# Battery_protector.net
KiCad netlist of a schematic drawn in Altium Designer
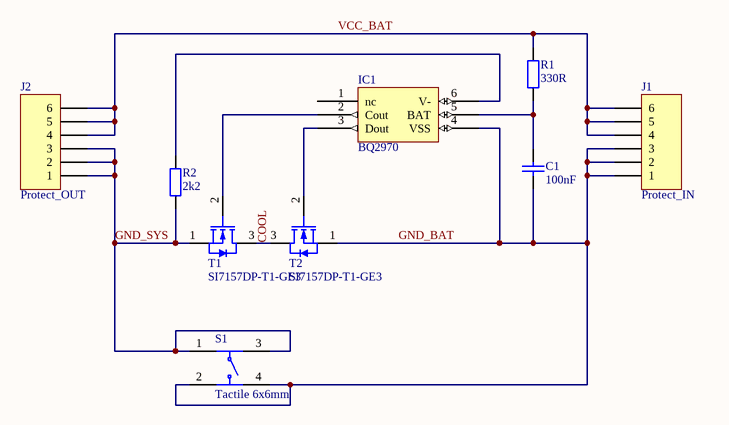
[diagram p0: Battery protector.SchDoc]

(export (version "E")
  (design (tool "Eeschema 10.0.6"))
  (components
    (comp (ref "C1")
      (value "100nF")
      (footprint "0603 cap")
      (description "Capacitor")
      (fields (field (name "VOLTAGE") ">5V"))
      (libsource (lib "IKSOR_LIB_main") (part "Capacitor NP"))
    )
    (comp (ref "IC1")
      (value "BQ2970")
      (footprint "PWSON-6")
      (description "Battery protection IC")
      (libsource (lib "IKSOR_LIB_main") (part "BQ2970"))
    )
    (comp (ref "J1")
      (value "Protect_IN")
      (footprint "HDR1X6")
      (description "Header, 6-Pin")
      (fields (field (name "PUBLISHER") "Altium Limited"))
      (libsource (lib "Miscellaneous Connectors") (part "Header 6"))
    )
    (comp (ref "J2")
      (value "Protect_OUT")
      (footprint "HDR1X6")
      (description "Header, 6-Pin")
      (fields (field (name "PUBLISHER") "Altium Limited"))
      (libsource (lib "") (part "Header 6_1"))
    )
    (comp (ref "R1")
      (value "330R")
      (footprint "0603 RES")
      (description "Resistor SMD")
      (fields (field (name "Comment") "Resistor generic"))
      (libsource (lib "IKSOR_LIB_main") (part "Resistor"))
    )
    (comp (ref "R2")
      (value "2k2")
      (footprint "0603 RES")
      (description "Resistor SMD")
      (fields (field (name "Comment") "Resistor generic"))
      (libsource (lib "IKSOR_LIB_main") (part "Resistor"))
    )
    (comp (ref "S1")
      (value "Tactile 6x6mm")
      (footprint "4301x20438x6")
      (description "WS-TASV 6x6 mm SMD")
      (fields
        (field (name "PARTNO") "430152043826")
        (field (name "MANUFACTURER") "Wurth Elektronik")
        (field (name "CREATED BY") "Baojun Chen")
      )
      (libsource (lib "ALTIUM-WS-TASV-rev16a") (part "WS-TASV, 430152043826"))
    )
    (comp (ref "T1")
      (value "SI7157DP-T1-GE3")
      (footprint "TDSON-8")
      (description "MOSFET N")
      (fields (field (name "Comment") "MOSFET-N"))
      (libsource (lib "IKSOR_LIB_main") (part "MOSFET-N"))
    )
    (comp (ref "T2")
      (value "SI7157DP-T1-GE3")
      (footprint "TDSON-8")
      (description "MOSFET N")
      (fields (field (name "Comment") "MOSFET-N"))
      (libsource (lib "IKSOR_LIB_main") (part "MOSFET-N"))
    )
  )
  (nets
    (net (code "1") (name "/COOL") (class "Default")
      (node (ref "T1") (pin "3") (pinfunction "D_3") (pintype "passive"))
      (node (ref "T2") (pin "3") (pinfunction "D_3") (pintype "passive"))
    )
    (net (code "2") (name "/GND_BAT") (class "Default")
      (node (ref "C1") (pin "1") (pinfunction "1_1") (pintype "passive"))
      (node (ref "IC1") (pin "4") (pinfunction "VSS_4") (pintype "bidirectional"))
      (node (ref "J1") (pin "1") (pinfunction "1_1") (pintype "passive"))
      (node (ref "J1") (pin "2") (pinfunction "2_2") (pintype "passive"))
      (node (ref "J1") (pin "3") (pinfunction "3_3") (pintype "passive"))
      (node (ref "S1") (pin "2") (pinfunction "2_2") (pintype "passive"))
      (node (ref "S1") (pin "4") (pinfunction "4_4") (pintype "passive"))
      (node (ref "T2") (pin "1") (pinfunction "S_1") (pintype "passive"))
    )
    (net (code "3") (name "/GND_SYS") (class "Default")
      (node (ref "J2") (pin "1") (pinfunction "1_1") (pintype "passive"))
      (node (ref "J2") (pin "2") (pinfunction "2_2") (pintype "passive"))
      (node (ref "J2") (pin "3") (pinfunction "3_3") (pintype "passive"))
      (node (ref "R2") (pin "1") (pinfunction "1_1") (pintype "passive"))
      (node (ref "S1") (pin "1") (pinfunction "1_1") (pintype "passive"))
      (node (ref "S1") (pin "3") (pinfunction "3_3") (pintype "passive"))
      (node (ref "T1") (pin "1") (pinfunction "S_1") (pintype "passive"))
    )
    (net (code "4") (name "/VCC_BAT") (class "Default")
      (node (ref "J1") (pin "4") (pinfunction "4_4") (pintype "passive"))
      (node (ref "J1") (pin "5") (pinfunction "5_5") (pintype "passive"))
      (node (ref "J1") (pin "6") (pinfunction "6_6") (pintype "passive"))
      (node (ref "J2") (pin "4") (pinfunction "4_4") (pintype "passive"))
      (node (ref "J2") (pin "5") (pinfunction "5_5") (pintype "passive"))
      (node (ref "J2") (pin "6") (pinfunction "6_6") (pintype "passive"))
      (node (ref "R1") (pin "2") (pinfunction "2_2") (pintype "passive"))
    )
    (net (code "5") (name "Net-(IC1-BAT)") (class "Default")
      (node (ref "C1") (pin "2") (pinfunction "2_2") (pintype "passive"))
      (node (ref "IC1") (pin "5") (pinfunction "BAT_5") (pintype "bidirectional"))
      (node (ref "R1") (pin "1") (pinfunction "1_1") (pintype "passive"))
    )
    (net (code "6") (name "Net-(IC1-Cout)") (class "Default")
      (node (ref "IC1") (pin "2") (pinfunction "Cout_2") (pintype "output"))
      (node (ref "T1") (pin "2") (pinfunction "G_2") (pintype "passive"))
    )
    (net (code "7") (name "Net-(IC1-Dout)") (class "Default")
      (node (ref "IC1") (pin "3") (pinfunction "Dout_3") (pintype "output"))
      (node (ref "T2") (pin "2") (pinfunction "G_2") (pintype "passive"))
    )
    (net (code "8") (name "Net-(IC1-V-)") (class "Default")
      (node (ref "IC1") (pin "6") (pinfunction "V-_6") (pintype "bidirectional"))
      (node (ref "R2") (pin "2") (pinfunction "2_2") (pintype "passive"))
    )
    (net (code "9") (name "unconnected-(IC1-nc-Pad1)") (class "Default")
      (node (ref "IC1") (pin "1") (pinfunction "nc_1") (pintype "passive"))
    )
  )
)
